# Circuit_schematic.net
KiCad netlist of a schematic drawn in Altium Designer
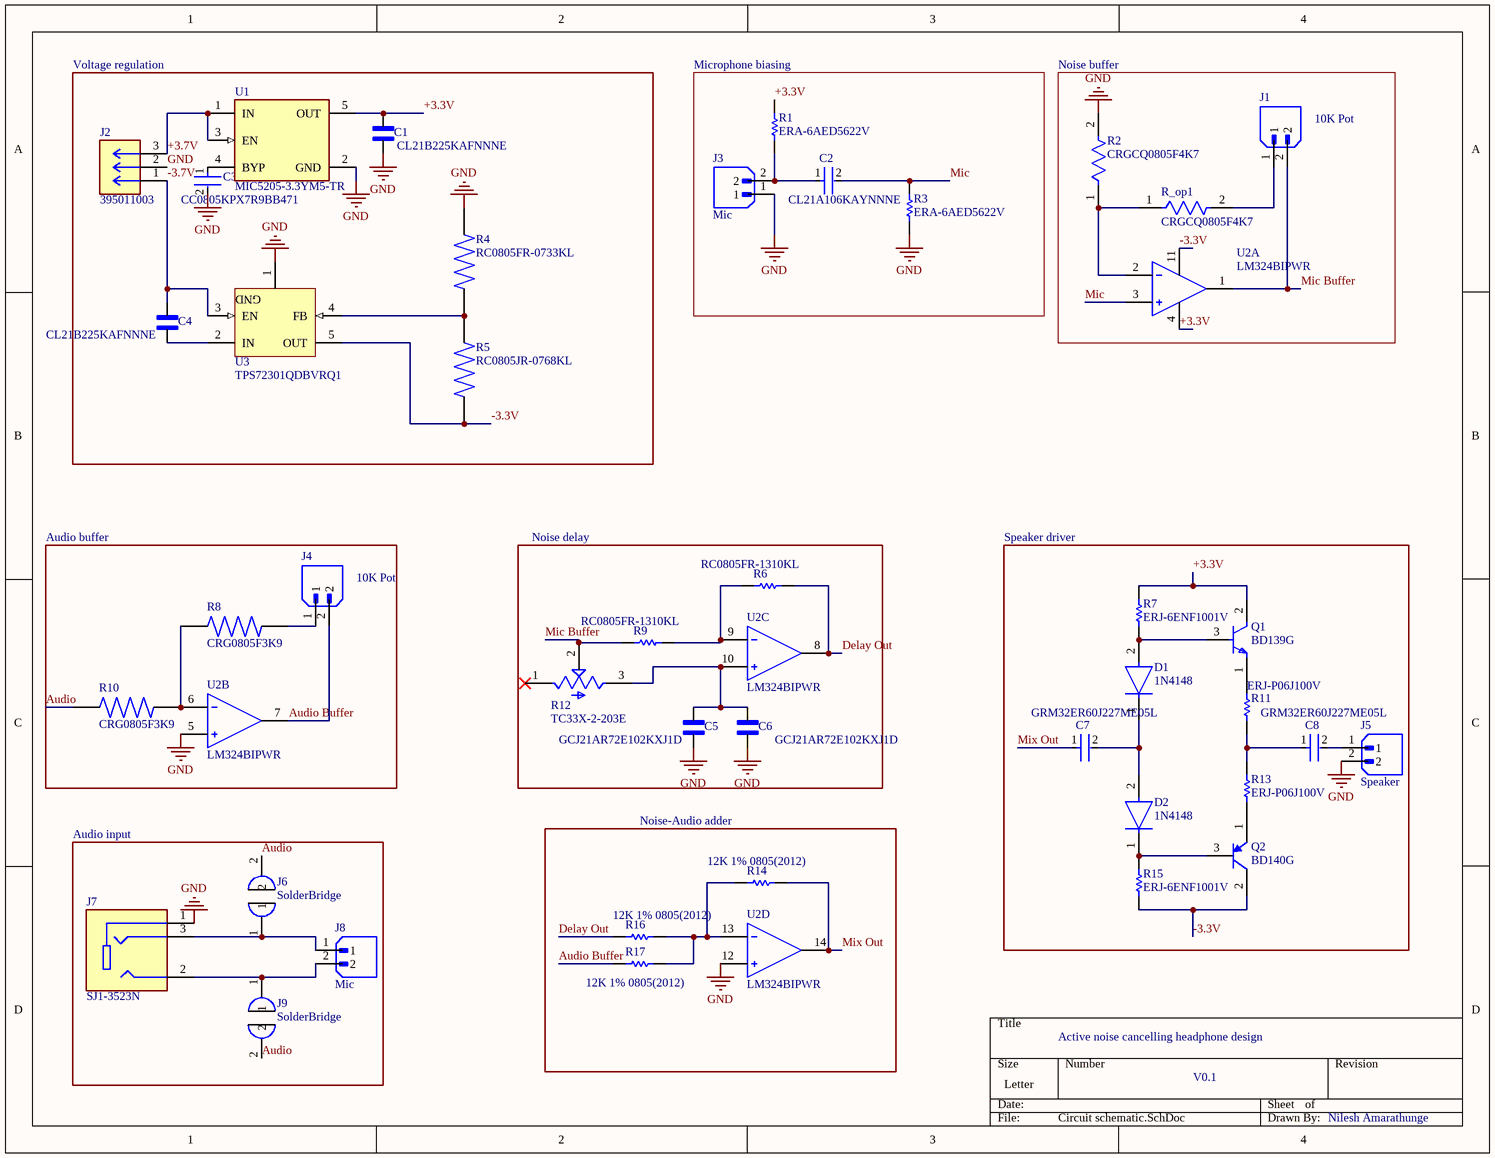
[diagram p0: Circuit schematic.SchDoc]

(export (version "E")
  (design (tool "Eeschema 10.0.6"))
  (components
    (comp (ref "C1")
      (value "CL21B225KAFNNNE")
      (footprint "CAPC2012X135N")
      (description "2.2 ÂµF Â±10% 25V Ceramic Capacitor X7R 0805 (2012 Metric)")
      (fields (field (name "MF") "Samsung") (field (name "LCSC PART #") "C19110"))
      (libsource (lib "CL21B225KAFNNNE") (part "CL21B225KAFNNNE"))
    )
    (comp (ref "C2")
      (value "CL21A106KAYNNNE")
      (footprint "FP-CL21-IPC_A")
      (description "CL21 Series 0805 10uF 25V ±10% Tolerance X5R Multilayer Ceramic Chip Capacitor")
      (fields (field (name "TOLERANCE") "10%") (field (name "LCSC PART #") "C15850"))
      (libsource (lib "Altium Content Vault") (part "b4654b650e69147ec39a6b967a45e02"))
    )
    (comp (ref "C3")
      (value "CC0805KPX7R9BB471")
      (footprint "FP-CC0805-0_85-MFG")
      (description "CC0805 470 pF X7R 10.00% 50 V")
      (fields
        (field (name "OCTOPART") "https://octopart.com/cc0805kpx7r9bb471-yageo-88496836")
        (field (name "TOLERANCE") "0.1")
      )
      (libsource (lib "Altium Content Vault") (part "11868f565c42a9108669ba33697ecf6"))
    )
    (comp (ref "C4")
      (value "CL21B225KAFNNNE")
      (footprint "CAPC2012X135N")
      (description "2.2 ÂµF Â±10% 25V Ceramic Capacitor X7R 0805 (2012 Metric)")
      (fields (field (name "MF") "Samsung") (field (name "LCSC PART #") "C19110"))
      (libsource (lib "CL21B225KAFNNNE") (part "CL21B225KAFNNNE"))
    )
    (comp (ref "C5")
      (value "GCJ21AR72E102KXJ1D")
      (footprint "CAPC2012X135N")
      (description "1nF Ceramic Capacitor X7R 0805 (2012 Metric)")
      (fields (field (name "MF") "Samsung") (field (name "MP") "CL21B225KAFNNNE"))
      (libsource (lib "CL21B225KAFNNNE") (part "CL21B225KAFNNNE"))
    )
    (comp (ref "C6")
      (value "GCJ21AR72E102KXJ1D")
      (footprint "CAPC2012X135N")
      (description "1nF Ceramic Capacitor X7R 0805 (2012 Metric)")
      (fields (field (name "MF") "Samsung") (field (name "MP") "CL21B225KAFNNNE"))
      (libsource (lib "CL21B225KAFNNNE") (part "CL21B225KAFNNNE"))
    )
    (comp (ref "C7")
      (value "GRM32ER60J227ME05L")
      (footprint "FP-GRM32E-0_3-MFG")
      (description "Chip Multilayer Ceramic Capacitors for General Purpose, 1210, 220uF, X5R, 15%, 20%, 6.3V")
      (fields (field (name "TOLERANCE") "20%") (field (name "LCSC PART #") "C469553"))
      (libsource (lib "Altium Content Vault") (part "b4654b650e69147ec39a6b967a45e02"))
    )
    (comp (ref "C8")
      (value "GRM32ER60J227ME05L")
      (footprint "FP-GRM32E-0_3-MFG")
      (description "Chip Multilayer Ceramic Capacitors for General Purpose, 1210, 220uF, X5R, 15%, 20%, 6.3V")
      (fields (field (name "TOLERANCE") "20%") (field (name "LCSC PART #") "C469553"))
      (libsource (lib "Altium Content Vault") (part "b4654b650e69147ec39a6b967a45e02"))
    )
    (comp (ref "D1")
      (value "1N4148")
      (footprint "FP-017AG-MFG")
      (description "DIODE GEN PURP 100V 200MA DO35")
      (fields (field (name "VOLTAGE") "100V"))
      (libsource (lib "Altium Content Vault") (part "d7152d700b627762746794eb795d46e"))
    )
    (comp (ref "D2")
      (value "1N4148")
      (footprint "FP-017AG-MFG")
      (description "DIODE GEN PURP 100V 200MA DO35")
      (fields (field (name "VOLTAGE") "100V"))
      (libsource (lib "Altium Content Vault") (part "d7152d700b627762746794eb795d46e"))
    )
    (comp (ref "J1")
      (value "10K Pot")
      (footprint "JST_B2B-XH-A")
      (fields
        (field (name "MF") "{'manufacturer': u'JST Sales America Inc.'}")
        (field (name "MP") "B2B-XH-A")
      )
      (libsource (lib "B2B-XH-A") (part "B2B-XH-A"))
    )
    (comp (ref "J2")
      (value "395011003")
      (footprint "CONN_39501-1003_MOL")
      (libsource (lib "395011003") (part "395011003"))
    )
    (comp (ref "J3")
      (value "Mic")
      (footprint "JST_B2B-XH-A")
      (fields
        (field (name "MF") "{'manufacturer': u'JST Sales America Inc.'}")
        (field (name "MP") "B2B-XH-A")
      )
      (libsource (lib "") (part "B2B-XH-A_2"))
    )
    (comp (ref "J4")
      (value "10K Pot")
      (footprint "JST_B2B-XH-A")
      (fields
        (field (name "MF") "{'manufacturer': u'JST Sales America Inc.'}")
        (field (name "MP") "B2B-XH-A")
      )
      (libsource (lib "B2B-XH-A") (part "B2B-XH-A"))
    )
    (comp (ref "J5")
      (value "Speaker")
      (footprint "JST_B2B-XH-A")
      (fields
        (field (name "MF") "{'manufacturer': u'JST Sales America Inc.'}")
        (field (name "MP") "B2B-XH-A")
      )
      (libsource (lib "") (part "B2B-XH-A_1"))
    )
    (comp (ref "J6")
      (value "SolderBridge")
      (footprint "PCBComponent_1")
      (libsource (lib "Solder bridge") (part "SolderBridge"))
    )
    (comp (ref "J7")
      (value "SJ1-3523N")
      (footprint "CUI_SJ1-3523N")
      (description "3.5 mm, Stereo, Right Angle, Through Hole, 3 Conductors, 0 Internal Switches, Audio Jack Connector")
      (fields (field (name "MF") "Same Sky") (field (name "LCSC PART #") "C20182914"))
      (libsource (lib "SJ1-3523N") (part "SJ1-3523N"))
    )
    (comp (ref "J8")
      (value "Mic")
      (footprint "JST_B2B-XH-A")
      (fields
        (field (name "MF") "{'manufacturer': u'JST Sales America Inc.'}")
        (field (name "MP") "B2B-XH-A")
      )
      (libsource (lib "") (part "B2B-XH-A_1"))
    )
    (comp (ref "J9")
      (value "SolderBridge")
      (footprint "PCBComponent_1")
      (libsource (lib "Solder bridge") (part "SolderBridge"))
    )
    (comp (ref "Q1")
      (value "BD139G")
      (footprint "FP-77-09-MFG")
      (libsource (lib "Altium Content Vault") (part "2239aae8d27e6eb6063ebea98827daf"))
    )
    (comp (ref "Q2")
      (value "BD140G")
      (footprint "ONSC-TO-225-3-77-09")
      (description "Plastic Medium-Power Silicon PNP Transistor, 3-Pin TO-225, Pb-Free, Bulk Box")
      (fields (field (name "MANUFACTURER") "On Semiconductor"))
      (libsource (lib "Altium Content Vault") (part "ONSC-PNP-E1C2B3-3"))
    )
    (comp (ref "R1")
      (value "ERA-6AED5622V")
      (footprint "RESC2013X60X40LL20T25")
      (fields (field (name "MANUFACTURER") "Panasonic") (field (name "LCSC PART #") "C445652"))
      (libsource (lib "Altium Content Vault") (part "RES"))
    )
    (comp (ref "R2")
      (value "CRGCQ0805F4K7")
      (footprint "FP-CRGCQ0805-IPC_C")
      (description "CRGCQ0805 4.7KΩ 0.125W ±100ppm/°C 1% 150V")
      (fields (field (name "TOLERANCE") "0.01") (field (name "MANUFACTURER") "TE Connectivity"))
      (libsource (lib "Altium Content Vault") (part "1029c3af85768c4190bb7ad29bc67b5"))
    )
    (comp (ref "R3")
      (value "ERA-6AED5622V")
      (footprint "RESC2013X60X40LL20T25")
      (fields (field (name "MANUFACTURER") "Panasonic") (field (name "LCSC PART #") "C445652"))
      (libsource (lib "Altium Content Vault") (part "RES"))
    )
    (comp (ref "R4")
      (value "RC0805FR-0733KL")
      (footprint "RESC2012X60N")
      (description "33 kOhms Â±1% 0.125W, 1/8W Chip Resistor 0805 (2012 Metric) Moisture Resistant Thick Film")
      (fields (field (name "MF") "Yageo") (field (name "LCSC PART #") "C141696"))
      (libsource (lib "RC0805FR-0733KL") (part "RC0805FR-0733KL"))
    )
    (comp (ref "R5")
      (value "RC0805JR-0768KL")
      (footprint "RESC2012X60N")
      (description "68 kOhms Â±5% 0.125W, 1/8W Chip Resistor 0805 (2012 Metric) Moisture Resistant Thick Film")
      (fields (field (name "MF") "Yageo") (field (name "LCSC PART #") "C137412"))
      (libsource (lib "RC0805JR-0768KL") (part "RC0805JR-0768KL"))
    )
    (comp (ref "R6")
      (value "RC0805FR-1310KL")
      (footprint "RESC2013X60X35ML10T20")
      (fields (field (name "MANUFACTURER") "Yageo") (field (name "LCSC PART #") "C191101"))
      (libsource (lib "Altium Content Vault") (part "RES"))
    )
    (comp (ref "R7")
      (value "ERJ-6ENF1001V")
      (footprint "RESC2013X70X40ML20T20")
      (description "Chip Resistor, 1 KOhm, +/- 1%, 0.125 W, -55 to 155 degC, 0805 (2012 Metric), RoHS, Tape and Reel")
      (fields (field (name "MANUFACTURER") "Panasonic") (field (name "LCSC PART #") "C79496"))
      (libsource (lib "Altium Content Vault") (part "RES-2"))
    )
    (comp (ref "R8")
      (value "CRG0805F3K9")
      (footprint "RESC2012X65N:RESC2012X65N")
      (description "CRG0805 1% 3K9")
      (fields (field (name "LCSC PART #") "C473293"))
      (libsource (lib "CRG0805F3K9") (part "CRG0805F3K9"))
    )
    (comp (ref "R9")
      (value "RC0805FR-1310KL")
      (footprint "RESC2013X60X35ML10T20")
      (fields (field (name "MANUFACTURER") "Yageo") (field (name "LCSC PART #") "C191101"))
      (libsource (lib "Altium Content Vault") (part "RES"))
    )
    (comp (ref "R10")
      (value "CRG0805F3K9")
      (footprint "RESC2012X65N:RESC2012X65N")
      (description "CRG0805 1% 3K9")
      (fields (field (name "LCSC PART #") "C473293"))
      (libsource (lib "CRG0805F3K9") (part "CRG0805F3K9"))
    )
    (comp (ref "R11")
      (value "ERJ-P06J100V")
      (footprint "RESC2013X70X40NL20T20")
      (fields (field (name "MANUFACTURER") "Panasonic") (field (name "LCSC PART #") "C6614492"))
      (libsource (lib "Altium Content Vault") (part "RES"))
    )
    (comp (ref "R12")
      (value "TC33X-2-203E")
      (footprint "TRIM_TC33X-2-203E")
      (description "20 kOhms 0.1W, 1/10W J Lead Surface Mount Trimmer Potentiometer Cermet 1 Turn Top Adjustment")
      (fields (field (name "MF") "Bourns") (field (name "DIGI-KEY_PART_NUMBER") "TC33X-2-203ECT-ND"))
      (libsource (lib "TC33X-2-203E") (part "TC33X-2-203E"))
    )
    (comp (ref "R13")
      (value "ERJ-P06J100V")
      (footprint "RESC2013X70X40NL20T20")
      (fields (field (name "MANUFACTURER") "Panasonic") (field (name "LCSC PART #") "C6614492"))
      (libsource (lib "Altium Content Vault") (part "RES"))
    )
    (comp (ref "R14")
      (value "12K 1% 0805(2012)")
      (footprint "RESC0805(2012)_L")
      (description "12K 0.125W 1% 0805 (2012 Metric)  SMD")
      (fields (field (name "TOLERANCE") "1 %") (field (name "POWER") "0.125 W"))
      (libsource (lib "Altium Content Vault") (part "RES"))
    )
    (comp (ref "R15")
      (value "ERJ-6ENF1001V")
      (footprint "RESC2013X70X40ML20T20")
      (description "Chip Resistor, 1 KOhm, +/- 1%, 0.125 W, -55 to 155 degC, 0805 (2012 Metric), RoHS, Tape and Reel")
      (fields (field (name "MANUFACTURER") "Panasonic") (field (name "LCSC PART #") "C79496"))
      (libsource (lib "Altium Content Vault") (part "RES-2"))
    )
    (comp (ref "R16")
      (value "12K 1% 0805(2012)")
      (footprint "RESC0805(2012)_L")
      (description "12K 0.125W 1% 0805 (2012 Metric)  SMD")
      (fields (field (name "TOLERANCE") "1 %") (field (name "POWER") "0.125 W"))
      (libsource (lib "Altium Content Vault") (part "RES"))
    )
    (comp (ref "R17")
      (value "12K 1% 0805(2012)")
      (footprint "RESC0805(2012)_L")
      (description "12K 0.125W 1% 0805 (2012 Metric)  SMD")
      (fields (field (name "TOLERANCE") "1 %") (field (name "POWER") "0.125 W"))
      (libsource (lib "Altium Content Vault") (part "RES"))
    )
    (comp (ref "R_op1")
      (value "CRGCQ0805F4K7")
      (footprint "FP-CRGCQ0805-IPC_C")
      (description "CRGCQ0805 4.7KΩ 0.125W ±100ppm/°C 1% 150V")
      (fields (field (name "TOLERANCE") "0.01") (field (name "MANUFACTURER") "TE Connectivity"))
      (libsource (lib "Altium Content Vault") (part "1029c3af85768c4190bb7ad29bc67b5"))
    )
    (comp (ref "U1")
      (value "MIC5205-3.3YM5-TR")
      (footprint "FP-M5-MFG")
      (description "IC REG LINEAR 3.3V 150MA SOT23-5")
      (fields
        (field (name "MANUFACTURER") "Microchip")
        (field (name "OCTOPART") "https://octopart.com/mic5205-3.3ym5-tr-microchip-66802130")
      )
      (libsource (lib "Altium Content Vault") (part "b2bb7f462d557aec50a251fc6568b2e"))
    )
    (comp (ref "U2")
      (value "LM324BIPWR")
      (footprint "FP-PW0014A-MFG")
      (description "LM324BIPWR Quad, 36-V, 1.2-MHz 3-mV offset voltage operational amplifier 14-TSSOP -40 to 85")
      (fields (field (name "LCSC PART #") "C5214225"))
      (libsource (lib "Altium Content Vault") (part "9bf548ecc718f14caecb3de0839edcd"))
    )
    (comp (ref "U3")
      (value "TPS72301QDBVRQ1")
      (footprint "DBV0005A_N")
      (fields (field (name "MANUFACTURER") "Texas Instruments") (field (name "LCSC PART #") "C2861780"))
      (libsource (lib "Altium Content Vault") (part "TI-TPS72301-5"))
    )
  )
  (nets
    (net (code "1") (name "/+3.3V") (class "Default")
      (node (ref "C1") (pin "2") (pinfunction "2_2") (pintype "passive"))
      (node (ref "Q1") (pin "2") (pinfunction "C_2") (pintype "passive"))
      (node (ref "R1") (pin "2") (pinfunction "2_2") (pintype "passive"))
      (node (ref "R7") (pin "2") (pinfunction "2_2") (pintype "passive"))
      (node (ref "U1") (pin "5") (pinfunction "OUT_5") (pintype "power_in"))
      (node (ref "U2") (pin "4") (pinfunction "VCC+_4") (pintype "power_in"))
    )
    (net (code "2") (name "/+3.7V") (class "Default")
      (node (ref "J2") (pin "3") (pinfunction "3_3") (pintype "passive"))
      (node (ref "U1") (pin "1") (pinfunction "IN_1") (pintype "power_in"))
      (node (ref "U1") (pin "3") (pinfunction "EN_3") (pintype "input"))
    )
    (net (code "3") (name "/-3.3V") (class "Default")
      (node (ref "Q2") (pin "2") (pinfunction "C_2") (pintype "passive"))
      (node (ref "R15") (pin "1") (pinfunction "1_1") (pintype "passive"))
      (node (ref "R5") (pin "2") (pinfunction "2_2") (pintype "passive"))
      (node (ref "U2") (pin "11") (pinfunction "VCC-_11") (pintype "power_in"))
      (node (ref "U3") (pin "5") (pinfunction "OUT_5") (pintype "power_in"))
    )
    (net (code "4") (name "/-3.7V") (class "Default")
      (node (ref "C4") (pin "2") (pinfunction "2_2") (pintype "passive"))
      (node (ref "J2") (pin "1") (pinfunction "1_1") (pintype "passive"))
      (node (ref "U3") (pin "3") (pinfunction "EN_3") (pintype "input"))
    )
    (net (code "5") (name "/Audio") (class "Default")
      (node (ref "J6") (pin "2") (pinfunction "2_2") (pintype "passive"))
      (node (ref "J9") (pin "2") (pinfunction "2_2") (pintype "passive"))
      (node (ref "R10") (pin "1") (pinfunction "1_1") (pintype "passive"))
    )
    (net (code "6") (name "/Audio Buffer") (class "Default")
      (node (ref "J4") (pin "2") (pinfunction "2_2") (pintype "passive"))
      (node (ref "R17") (pin "1") (pinfunction "1_1") (pintype "passive"))
      (node (ref "U2") (pin "7") (pinfunction "2OUT_7") (pintype "passive"))
    )
    (net (code "7") (name "/Delay Out") (class "Default")
      (node (ref "R16") (pin "1") (pinfunction "1_1") (pintype "passive"))
      (node (ref "R6") (pin "2") (pinfunction "2_2") (pintype "passive"))
      (node (ref "U2") (pin "8") (pinfunction "3OUT_8") (pintype "passive"))
    )
    (net (code "8") (name "/Mic") (class "Default")
      (node (ref "C2") (pin "2") (pinfunction "2_2") (pintype "passive"))
      (node (ref "R3") (pin "2") (pinfunction "2_2") (pintype "passive"))
      (node (ref "U2") (pin "3") (pinfunction "1IN+_3") (pintype "tri_state"))
    )
    (net (code "9") (name "/Mic Buffer") (class "Default")
      (node (ref "J1") (pin "2") (pinfunction "2_2") (pintype "passive"))
      (node (ref "R12") (pin "2") (pinfunction "W_2") (pintype "passive"))
      (node (ref "R9") (pin "1") (pinfunction "1_1") (pintype "passive"))
      (node (ref "U2") (pin "1") (pinfunction "1OUT_1") (pintype "passive"))
    )
    (net (code "10") (name "/Mix Out") (class "Default")
      (node (ref "C7") (pin "1") (pinfunction "1_1") (pintype "passive"))
      (node (ref "R14") (pin "2") (pinfunction "2_2") (pintype "passive"))
      (node (ref "U2") (pin "14") (pinfunction "4OUT_14") (pintype "passive"))
    )
    (net (code "11") (name "GND") (class "Default")
      (node (ref "C1") (pin "1") (pinfunction "1_1") (pintype "passive"))
      (node (ref "C3") (pin "2") (pinfunction "2_2") (pintype "passive"))
      (node (ref "C5") (pin "1") (pinfunction "1_1") (pintype "passive"))
      (node (ref "C6") (pin "1") (pinfunction "1_1") (pintype "passive"))
      (node (ref "J2") (pin "2") (pinfunction "2_2") (pintype "passive"))
      (node (ref "J3") (pin "1") (pinfunction "1_1") (pintype "passive"))
      (node (ref "J5") (pin "2") (pinfunction "2_2") (pintype "passive"))
      (node (ref "J7") (pin "1") (pinfunction "1_1") (pintype "passive"))
      (node (ref "R2") (pin "2") (pinfunction "2_2") (pintype "passive"))
      (node (ref "R3") (pin "1") (pinfunction "1_1") (pintype "passive"))
      (node (ref "R4") (pin "1") (pinfunction "1_1") (pintype "passive"))
      (node (ref "U1") (pin "2") (pinfunction "GND_2") (pintype "power_in"))
      (node (ref "U2") (pin "12") (pinfunction "4IN+_12") (pintype "tri_state"))
      (node (ref "U2") (pin "5") (pinfunction "2IN+_5") (pintype "tri_state"))
      (node (ref "U3") (pin "1") (pinfunction "GND_1") (pintype "power_in"))
    )
    (net (code "12") (name "Net-(C2-Pad1)") (class "Default")
      (node (ref "C2") (pin "1") (pinfunction "1_1") (pintype "passive"))
      (node (ref "J3") (pin "2") (pinfunction "2_2") (pintype "passive"))
      (node (ref "R1") (pin "1") (pinfunction "1_1") (pintype "passive"))
    )
    (net (code "13") (name "Net-(C8-Pad1)") (class "Default")
      (node (ref "C8") (pin "1") (pinfunction "1_1") (pintype "passive"))
      (node (ref "R11") (pin "1") (pinfunction "1_1") (pintype "passive"))
      (node (ref "R13") (pin "2") (pinfunction "2_2") (pintype "passive"))
    )
    (net (code "14") (name "Net-(C8-Pad2)") (class "Default")
      (node (ref "C8") (pin "2") (pinfunction "2_2") (pintype "passive"))
      (node (ref "J5") (pin "1") (pinfunction "1_1") (pintype "passive"))
    )
    (net (code "15") (name "Net-(D1-A)") (class "Default")
      (node (ref "D1") (pin "2") (pinfunction "A_2") (pintype "passive"))
      (node (ref "Q1") (pin "3") (pinfunction "B_3") (pintype "passive"))
      (node (ref "R7") (pin "1") (pinfunction "1_1") (pintype "passive"))
    )
    (net (code "16") (name "Net-(D1-C)") (class "Default")
      (node (ref "C7") (pin "2") (pinfunction "2_2") (pintype "passive"))
      (node (ref "D1") (pin "1") (pinfunction "C_1") (pintype "passive"))
      (node (ref "D2") (pin "2") (pinfunction "A_2") (pintype "passive"))
    )
    (net (code "17") (name "Net-(D2-C)") (class "Default")
      (node (ref "D2") (pin "1") (pinfunction "C_1") (pintype "passive"))
      (node (ref "Q2") (pin "3") (pinfunction "B_3") (pintype "passive"))
      (node (ref "R15") (pin "2") (pinfunction "2_2") (pintype "passive"))
    )
    (net (code "18") (name "Net-(J1-Pad1)") (class "Default")
      (node (ref "J1") (pin "1") (pinfunction "1_1") (pintype "passive"))
      (node (ref "R_op1") (pin "2") (pinfunction "2_2") (pintype "passive"))
    )
    (net (code "19") (name "Net-(J4-Pad1)") (class "Default")
      (node (ref "J4") (pin "1") (pinfunction "1_1") (pintype "passive"))
      (node (ref "R8") (pin "2") (pinfunction "2_2") (pintype "passive"))
    )
    (net (code "20") (name "Net-(J6-Pad1)") (class "Default")
      (node (ref "J6") (pin "1") (pinfunction "1_1") (pintype "passive"))
      (node (ref "J7") (pin "3") (pinfunction "3_3") (pintype "passive"))
      (node (ref "J8") (pin "1") (pinfunction "1_1") (pintype "passive"))
    )
    (net (code "21") (name "Net-(J7-Pad2)") (class "Default")
      (node (ref "J7") (pin "2") (pinfunction "2_2") (pintype "passive"))
      (node (ref "J8") (pin "2") (pinfunction "2_2") (pintype "passive"))
      (node (ref "J9") (pin "1") (pinfunction "1_1") (pintype "passive"))
    )
    (net (code "22") (name "Net-(Q1-E)") (class "Default")
      (node (ref "Q1") (pin "1") (pinfunction "E_1") (pintype "passive"))
      (node (ref "R11") (pin "2") (pinfunction "2_2") (pintype "passive"))
    )
    (net (code "23") (name "Net-(Q2-E)") (class "Default")
      (node (ref "Q2") (pin "1") (pinfunction "E_1") (pintype "passive"))
      (node (ref "R13") (pin "1") (pinfunction "1_1") (pintype "passive"))
    )
    (net (code "24") (name "Net-(R12-CW)") (class "Default")
      (node (ref "C5") (pin "2") (pinfunction "2_2") (pintype "passive"))
      (node (ref "C6") (pin "2") (pinfunction "2_2") (pintype "passive"))
      (node (ref "R12") (pin "3") (pinfunction "CW_3") (pintype "passive"))
      (node (ref "U2") (pin "10") (pinfunction "3IN+_10") (pintype "tri_state"))
    )
    (net (code "25") (name "Net-(U1-BYP)") (class "Default")
      (node (ref "C3") (pin "1") (pinfunction "1_1") (pintype "passive"))
      (node (ref "U1") (pin "4") (pinfunction "BYP_4") (pintype "passive"))
    )
    (net (code "26") (name "Net-(U2A-1IN-)") (class "Default")
      (node (ref "R2") (pin "1") (pinfunction "1_1") (pintype "passive"))
      (node (ref "R_op1") (pin "1") (pinfunction "1_1") (pintype "passive"))
      (node (ref "U2") (pin "2") (pinfunction "1IN-_2") (pintype "tri_state"))
    )
    (net (code "27") (name "Net-(U2B-2IN-)") (class "Default")
      (node (ref "R10") (pin "2") (pinfunction "2_2") (pintype "passive"))
      (node (ref "R8") (pin "1") (pinfunction "1_1") (pintype "passive"))
      (node (ref "U2") (pin "6") (pinfunction "2IN-_6") (pintype "tri_state"))
    )
    (net (code "28") (name "Net-(U2C-3IN-)") (class "Default")
      (node (ref "R6") (pin "1") (pinfunction "1_1") (pintype "passive"))
      (node (ref "R9") (pin "2") (pinfunction "2_2") (pintype "passive"))
      (node (ref "U2") (pin "9") (pinfunction "3IN-_9") (pintype "tri_state"))
    )
    (net (code "29") (name "Net-(U2D-4IN-)") (class "Default")
      (node (ref "R14") (pin "1") (pinfunction "1_1") (pintype "passive"))
      (node (ref "R16") (pin "2") (pinfunction "2_2") (pintype "passive"))
      (node (ref "R17") (pin "2") (pinfunction "2_2") (pintype "passive"))
      (node (ref "U2") (pin "13") (pinfunction "4IN-_13") (pintype "tri_state"))
    )
    (net (code "30") (name "Net-(U3-FB)") (class "Default")
      (node (ref "R4") (pin "2") (pinfunction "2_2") (pintype "passive"))
      (node (ref "R5") (pin "1") (pinfunction "1_1") (pintype "passive"))
      (node (ref "U3") (pin "4") (pinfunction "FB_4") (pintype "input"))
    )
    (net (code "31") (name "Net-(U3-IN)") (class "Default")
      (node (ref "C4") (pin "1") (pinfunction "1_1") (pintype "passive"))
      (node (ref "U3") (pin "2") (pinfunction "IN_2") (pintype "power_in"))
    )
    (net (code "32") (name "unconnected-(R12-CCW-Pad1)") (class "Default")
      (node (ref "R12") (pin "1") (pinfunction "CCW_1") (pintype "passive+no_connect"))
    )
  )
)
